# 12V_5V_SMPS.net
KiCad netlist of a schematic drawn in Altium Designer
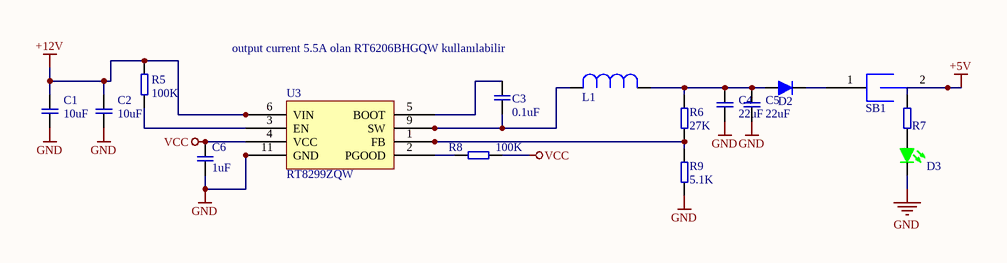
[diagram p0: 12V_5V_SMPS.SchDoc]

(export (version "E")
  (design (tool "Eeschema 10.0.6"))
  (components
    (comp (ref "C1")
      (value "10uF")
      (footprint "C0805")
      (description "CAP CER 10UF 25V X5R 0805")
      (fields (field (name "PART NUMBER") "CC0805KKX5R8BB106") (field (name "VOLTAGE") "25V"))
      (libsource (lib "anayurt") (part "CAP"))
    )
    (comp (ref "C2")
      (value "10uF")
      (footprint "C0805")
      (description "CAP CER 10UF 25V X5R 0805")
      (fields (field (name "PART NUMBER") "CC0805KKX5R8BB106") (field (name "VOLTAGE") "25V"))
      (libsource (lib "anayurt") (part "CAP"))
    )
    (comp (ref "C3")
      (value "0.1uF")
      (footprint "C0402")
      (description "CAP CER 0.1UF 25V X7R 0402")
      (fields (field (name "PART NUMBER") "04023C104KAT2A") (field (name "VOLTAGE") "25V"))
      (libsource (lib "anayurt") (part "CAP"))
    )
    (comp (ref "C4")
      (value "22uF")
      (footprint "C1210")
      (description "CAP CER 22UF 25V X5R 1210")
      (fields (field (name "PART NUMBER") "CL32A226KAJNNWE") (field (name "VOLTAGE") "25V"))
      (libsource (lib "anayurt") (part "CAP"))
    )
    (comp (ref "C5")
      (value "22uF")
      (footprint "C1210")
      (description "CAP CER 22UF 25V X5R 1210")
      (fields (field (name "PART NUMBER") "CL32A226KAJNNWE") (field (name "VOLTAGE") "25V"))
      (libsource (lib "anayurt") (part "CAP"))
    )
    (comp (ref "C6")
      (value "1uF")
      (footprint "C0603")
      (description "CAP CER 1UF 25V X7R 0603")
      (fields (field (name "PART NUMBER") "CGA3E1X7R1E105M080AC") (field (name "VOLTAGE") "25V"))
      (libsource (lib "anayurt") (part "CAP"))
    )
    (comp (ref "D2")
      (value "TSSA3U60 R3G")
      (footprint "TAIWAN_TSSA3U60 R3G")
      (description "DIODE SCHOTTKY 60V 3A DO214AC")
      (fields (field (name "MANUFACTURER") "Taiwan Semiconductor Corporation"))
      (libsource (lib "anayurt") (part "DIODE"))
    )
    (comp (ref "D3")
      (value "SML-LX0603GW-TR")
      (footprint "L0603")
      (description "LED GREEN DIFFUSED SMD")
      (fields (field (name "MANUFACTURER") "Lumex Opto/Components Inc."))
      (libsource (lib "anayurt") (part "LED_GREEN"))
    )
    (comp (ref "L1")
      (value "XAL6060-682MEB")
      (footprint "CC_XAL6060-682MEB")
      (description "6.8uH 9A 20.8mOhm Inductor")
      (fields (field (name "MANUFACTURER") "Coilcraft"))
      (libsource (lib "anayurt") (part "PINDC"))
    )
    (comp (ref "R5")
      (value "100K")
      (footprint "R0402")
      (description "RES SMD 100K OHM 1% 1/16W 0402")
      (fields (field (name "PART NUMBER") "RC0402FR-07100KL") (field (name "TOLERANCE") "1%"))
      (libsource (lib "anayurt") (part "RES"))
    )
    (comp (ref "R6")
      (value "27K")
      (footprint "R0402")
      (description "RES 27K OHM 1% 1/16W 0402")
      (fields (field (name "PART NUMBER") "RMCF0402FT27K0") (field (name "TOLERANCE") "±1%"))
      (libsource (lib "anayurt") (part "RES"))
    )
    (comp (ref "R7")
      (value "330R")
      (footprint "R0603")
      (description "RES 330 OHM 1% 1/10W 0603")
      (fields (field (name "PART NUMBER") "RMCF0603FT330R") (field (name "TOLERANCE") "0.1%"))
      (libsource (lib "anayurt") (part "RES"))
    )
    (comp (ref "R8")
      (value "100K")
      (footprint "R0402")
      (description "RES SMD 100K OHM 1% 1/16W 0402")
      (fields (field (name "PART NUMBER") "RC0402FR-07100KL") (field (name "TOLERANCE") "1%"))
      (libsource (lib "anayurt") (part "RES"))
    )
    (comp (ref "R9")
      (value "5.1K")
      (footprint "R0402")
      (description "RES 5.1K OHM 1% 1/16W 0402")
      (fields (field (name "PART NUMBER") "RC0402FR-075K1L") (field (name "TOLERANCE") "1%"))
      (libsource (lib "anayurt") (part "RES"))
    )
    (comp (ref "SB1")
      (value "Jumper")
      (footprint "SB.0805")
      (description "0805 Solder Bridge")
      (fields (field (name "PART NUMBER") "Solder Bridge0805"))
      (libsource (lib "anayurt") (part "Bridge"))
    )
    (comp (ref "U3")
      (value "RT8299ZQW")
      (footprint "RT8299ZQW")
      (description "IC REG BUCK ADJUSTABLE 3A 10WDFN")
      (fields (field (name "MANUFACTURER") "Richtek USA Inc."))
      (libsource (lib "anayurt") (part "RT8299ZQW"))
    )
  )
  (nets
    (net (code "1") (name "+5V") (class "Default")
      (node (ref "R7") (pin "2") (pinfunction "2_2") (pintype "passive"))
      (node (ref "SB1") (pin "2") (pinfunction "2_2") (pintype "passive"))
    )
    (net (code "2") (name "+12V") (class "Default")
      (node (ref "C1") (pin "1") (pinfunction "1_1") (pintype "passive"))
      (node (ref "C2") (pin "1") (pinfunction "1_1") (pintype "passive"))
      (node (ref "R5") (pin "2") (pinfunction "2_2") (pintype "passive"))
      (node (ref "U3") (pin "6") (pinfunction "VIN_6") (pintype "passive"))
      (node (ref "U3") (pin "7") (pinfunction "VIN_7") (pintype "passive"))
    )
    (net (code "3") (name "GND") (class "Default")
      (node (ref "C1") (pin "2") (pinfunction "2_2") (pintype "passive"))
      (node (ref "C2") (pin "2") (pinfunction "2_2") (pintype "passive"))
      (node (ref "C4") (pin "1") (pinfunction "1_1") (pintype "passive"))
      (node (ref "C5") (pin "1") (pinfunction "1_1") (pintype "passive"))
      (node (ref "C6") (pin "1") (pinfunction "1_1") (pintype "passive"))
      (node (ref "D3") (pin "C") (pinfunction "C_C") (pintype "passive"))
      (node (ref "R9") (pin "2") (pinfunction "2_2") (pintype "passive"))
      (node (ref "U3") (pin "10") (pinfunction "GND_10") (pintype "passive"))
      (node (ref "U3") (pin "11") (pinfunction "GND_11") (pintype "passive"))
    )
    (net (code "4") (name "Net-(C3-Pad1)") (class "Default")
      (node (ref "C3") (pin "1") (pinfunction "1_1") (pintype "passive"))
      (node (ref "L1") (pin "2") (pinfunction "2_2") (pintype "passive"))
      (node (ref "U3") (pin "8") (pinfunction "SW_8") (pintype "passive"))
      (node (ref "U3") (pin "9") (pinfunction "SW_9") (pintype "passive"))
    )
    (net (code "5") (name "Net-(C4-Pad2)") (class "Default")
      (node (ref "C4") (pin "2") (pinfunction "2_2") (pintype "passive"))
      (node (ref "C5") (pin "2") (pinfunction "2_2") (pintype "passive"))
      (node (ref "D2") (pin "A") (pinfunction "A_A") (pintype "passive"))
      (node (ref "L1") (pin "1") (pinfunction "1_1") (pintype "passive"))
      (node (ref "R6") (pin "2") (pinfunction "2_2") (pintype "passive"))
    )
    (net (code "6") (name "Net-(D2-PadC)") (class "Default")
      (node (ref "D2") (pin "C") (pinfunction "C_C") (pintype "passive"))
      (node (ref "SB1") (pin "1") (pinfunction "1_1") (pintype "passive"))
    )
    (net (code "7") (name "Net-(D3-PadA)") (class "Default")
      (node (ref "D3") (pin "A") (pinfunction "A_A") (pintype "passive"))
      (node (ref "R7") (pin "1") (pinfunction "1_1") (pintype "passive"))
    )
    (net (code "8") (name "Net-(U3-BOOT)") (class "Default")
      (node (ref "C3") (pin "2") (pinfunction "2_2") (pintype "passive"))
      (node (ref "U3") (pin "5") (pinfunction "BOOT_5") (pintype "passive"))
    )
    (net (code "9") (name "Net-(U3-EN)") (class "Default")
      (node (ref "R5") (pin "1") (pinfunction "1_1") (pintype "passive"))
      (node (ref "U3") (pin "3") (pinfunction "EN_3") (pintype "passive"))
    )
    (net (code "10") (name "Net-(U3-FB)") (class "Default")
      (node (ref "R6") (pin "1") (pinfunction "1_1") (pintype "passive"))
      (node (ref "R9") (pin "1") (pinfunction "1_1") (pintype "passive"))
      (node (ref "U3") (pin "1") (pinfunction "FB_1") (pintype "passive"))
    )
    (net (code "11") (name "Net-(U3-PGOOD)") (class "Default")
      (node (ref "R8") (pin "2") (pinfunction "2_2") (pintype "passive"))
      (node (ref "U3") (pin "2") (pinfunction "PGOOD_2") (pintype "power_in"))
    )
    (net (code "12") (name "VCC") (class "Default")
      (node (ref "C6") (pin "2") (pinfunction "2_2") (pintype "passive"))
      (node (ref "R8") (pin "1") (pinfunction "1_1") (pintype "passive"))
      (node (ref "U3") (pin "4") (pinfunction "VCC_4") (pintype "power_in"))
    )
  )
)
